# Microcontroller.net
KiCad netlist of a schematic drawn in Altium Designer
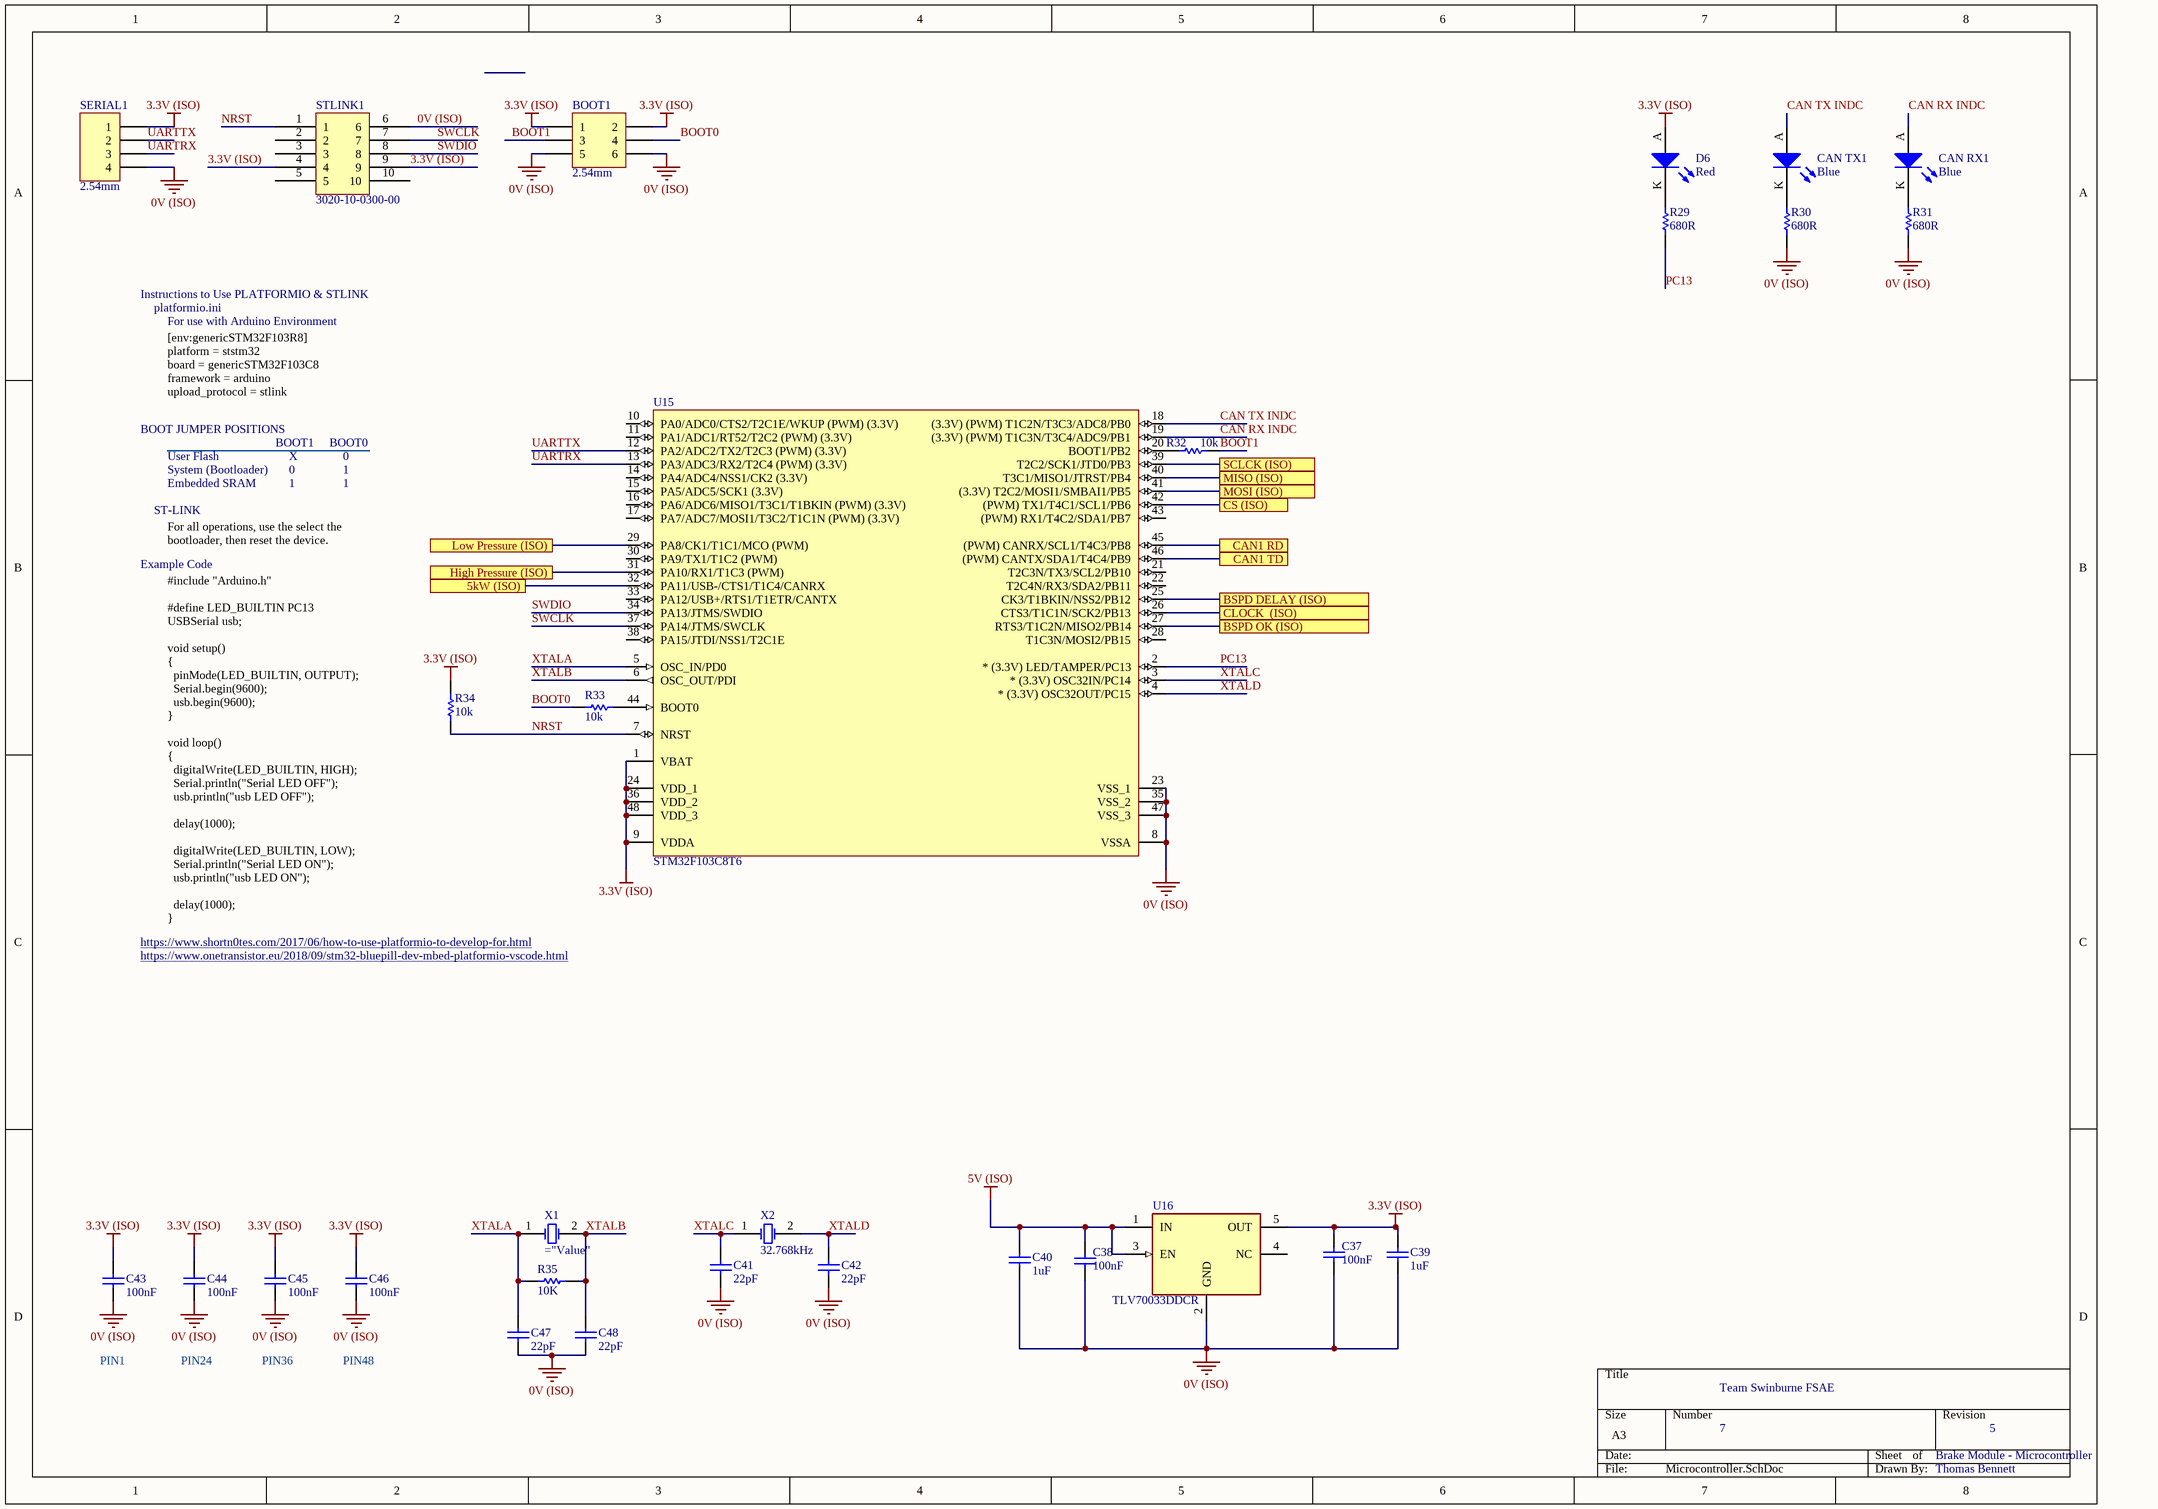
[diagram p0: Microcontroller.SchDoc]

(export (version "E")
  (design (tool "Eeschema 10.0.6"))
  (components
    (comp (ref "BOOT1")
      (value "2.54mm")
      (footprint "TH 2.54mm Header 2x3")
      (fields (field (name "PART NUMBER") "TH 2.54mm Header 2x3") (field (name "CONTACT") "NA"))
      (libsource (lib "ts_20-standard-connectors") (part "Header 2x3"))
    )
    (comp (ref "C37")
      (value "100nF")
      (footprint "C0603")
      (fields (field (name "PART NUMBER") "CC0603ZPY5V9BB104") (field (name "TOLERANCE") "5%"))
      (libsource (lib "AMS_Component_Library") (part "Capacitor"))
    )
    (comp (ref "C38")
      (value "100nF")
      (footprint "C0603")
      (fields (field (name "PART NUMBER") "CC0603ZPY5V9BB104") (field (name "TOLERANCE") "5%"))
      (libsource (lib "AMS_Component_Library") (part "Capacitor"))
    )
    (comp (ref "C39")
      (value "1uF")
      (footprint "0603")
      (fields
        (field (name "PART NUMBER") "GRT188R61H105ME13D")
        (field (name "TOLERANCE") "20%")
        (field (name "MANUFACTURER") "muRata")
      )
      (libsource (lib "ts_20-standard-library") (part "Capacitor"))
    )
    (comp (ref "C40")
      (value "1uF")
      (footprint "0603")
      (fields
        (field (name "PART NUMBER") "GRT188R61H105ME13D")
        (field (name "TOLERANCE") "20%")
        (field (name "MANUFACTURER") "muRata")
      )
      (libsource (lib "ts_20-standard-library") (part "Capacitor"))
    )
    (comp (ref "C41")
      (value "22pF")
      (footprint "C0603")
      (fields (field (name "PART NUMBER") "CC0603JPNPO9BN220") (field (name "TOLERANCE") "5%"))
      (libsource (lib "AMS_Component_Library") (part "Capacitor"))
    )
    (comp (ref "C42")
      (value "22pF")
      (footprint "C0603")
      (fields (field (name "PART NUMBER") "CC0603JPNPO9BN220") (field (name "TOLERANCE") "5%"))
      (libsource (lib "AMS_Component_Library") (part "Capacitor"))
    )
    (comp (ref "C43")
      (value "100nF")
      (footprint "C0603")
      (fields (field (name "PART NUMBER") "CC0603ZPY5V9BB104") (field (name "TOLERANCE") "5%"))
      (libsource (lib "AMS_Component_Library") (part "Capacitor"))
    )
    (comp (ref "C44")
      (value "100nF")
      (footprint "C0603")
      (fields (field (name "PART NUMBER") "CC0603ZPY5V9BB104") (field (name "TOLERANCE") "5%"))
      (libsource (lib "AMS_Component_Library") (part "Capacitor"))
    )
    (comp (ref "C45")
      (value "100nF")
      (footprint "C0603")
      (fields (field (name "PART NUMBER") "CC0603ZPY5V9BB104") (field (name "TOLERANCE") "5%"))
      (libsource (lib "AMS_Component_Library") (part "Capacitor"))
    )
    (comp (ref "C46")
      (value "100nF")
      (footprint "C0603")
      (fields (field (name "PART NUMBER") "CC0603ZPY5V9BB104") (field (name "TOLERANCE") "5%"))
      (libsource (lib "AMS_Component_Library") (part "Capacitor"))
    )
    (comp (ref "C47")
      (value "22pF")
      (footprint "C0603")
      (fields (field (name "PART NUMBER") "CC0603JPNPO9BN220") (field (name "TOLERANCE") "5%"))
      (libsource (lib "AMS_Component_Library") (part "Capacitor"))
    )
    (comp (ref "C48")
      (value "22pF")
      (footprint "C0603")
      (fields (field (name "PART NUMBER") "CC0603JPNPO9BN220") (field (name "TOLERANCE") "5%"))
      (libsource (lib "AMS_Component_Library") (part "Capacitor"))
    )
    (comp (ref "CAN RX1")
      (value "Blue")
      (footprint "0805 LED")
      (description "LED BLUE CLEAR 2012 SMD")
      (fields
        (field (name "PART NUMBER") "SML-MN2BCTT86C")
        (field (name "MANUFACTURER") "ROHM Semiconductor")
      )
      (libsource (lib "ts_20-standard-library") (part "LED"))
    )
    (comp (ref "CAN TX1")
      (value "Blue")
      (footprint "0805 LED")
      (description "LED BLUE CLEAR 2012 SMD")
      (fields
        (field (name "PART NUMBER") "SML-MN2BCTT86C")
        (field (name "MANUFACTURER") "ROHM Semiconductor")
      )
      (libsource (lib "ts_20-standard-library") (part "LED"))
    )
    (comp (ref "D6")
      (value "Red")
      (footprint "0805 LED")
      (description "Red LED Indication - Discrete 1.75V 0805 (2012 Metric)")
      (fields (field (name "PART NUMBER") "SML-210LTT86") (field (name "MANUFACTURER") "ROHM Semiconductor"))
      (libsource (lib "ts_20-standard-library") (part "LED"))
    )
    (comp (ref "R29")
      (value "680R")
      (footprint "R0603")
      (fields (field (name "PART NUMBER") "RCP0603B680RGEA") (field (name "TOLERANCE") "2%"))
      (libsource (lib "AMS_Component_Library") (part "Resistor"))
    )
    (comp (ref "R30")
      (value "680R")
      (footprint "R0603")
      (fields (field (name "PART NUMBER") "RCP0603B680RGEA") (field (name "TOLERANCE") "2%"))
      (libsource (lib "AMS_Component_Library") (part "Resistor"))
    )
    (comp (ref "R31")
      (value "680R")
      (footprint "R0603")
      (fields (field (name "PART NUMBER") "RCP0603B680RGEA") (field (name "TOLERANCE") "2%"))
      (libsource (lib "AMS_Component_Library") (part "Resistor"))
    )
    (comp (ref "R32")
      (value "10k")
      (footprint "0805")
      (fields
        (field (name "PART NUMBER") "RC0805FR0710KL")
        (field (name "MANUFACTURER") "YAGEO")
        (field (name "TOLERANCE") "0.01")
      )
      (libsource (lib "ts_20-standard-library") (part "Resistor"))
    )
    (comp (ref "R33")
      (value "10k")
      (footprint "0805")
      (fields
        (field (name "PART NUMBER") "RC0805FR0710KL")
        (field (name "MANUFACTURER") "YAGEO")
        (field (name "TOLERANCE") "0.01")
      )
      (libsource (lib "ts_20-standard-library") (part "Resistor"))
    )
    (comp (ref "R34")
      (value "10k")
      (footprint "0805")
      (fields
        (field (name "PART NUMBER") "RC0805FR0710KL")
        (field (name "MANUFACTURER") "YAGEO")
        (field (name "TOLERANCE") "0.01")
      )
      (libsource (lib "ts_20-standard-library") (part "Resistor"))
    )
    (comp (ref "R35")
      (value "10K")
      (footprint "R0603")
      (fields (field (name "PART NUMBER") "RA73F1J10KBTD") (field (name "TOLERANCE") "0.1%"))
      (libsource (lib "AMS_Component_Library") (part "Resistor"))
    )
    (comp (ref "SERIAL1")
      (value "2.54mm")
      (footprint "TH 2.54mm Header 1x4")
      (fields (field (name "PART NUMBER") "TH 2.54mm Header 1x4") (field (name "CONTACT") "NA"))
      (libsource (lib "ts_20-standard-connectors") (part "Header 1x4"))
    )
    (comp (ref "STLINK1")
      (value "3020-10-0300-00")
      (footprint "3020-10-0300-00")
      (description "Header SMD 2.54mm 2x05")
      (libsource (lib "AMS_Component_Library") (part "3020-10-0300-00"))
    )
    (comp (ref "U15")
      (value "STM32F103C8T6")
      (footprint "STM 48-LQFP")
      (description "ARM® Cortex®-M3 STM32F1 Microcontroller IC 32-Bit 72MHz 64KB (64K x 8) FLASH")
      (fields
        (field (name "MANUFACTURER") "STMicroelectronics")
        (field (name "DIGIKEY PART NUMBER") "497-6063-ND")
      )
      (libsource (lib "ts_20-standard-library") (part "STM32F103C8T6"))
    )
    (comp (ref "U16")
      (value "TLV70033DDCR")
      (footprint "FP-DDC0005A-IPC_B")
      (description "Fixed Positive LDO Regulator, 3.3V, 0.25V Dropout, PMOS, PDSO5")
      (libsource (lib "Team Swinburne") (part "c6f9311032385d92892323ecfb9e53c"))
    )
    (comp (ref "X1")
      (value "~")
      (footprint "ECS-80-18-30-JGN-TR")
      (description "Crystal 8MHz")
      (fields (field (name "PART NUMBER") "ECS-80-18-30-JGN-TR"))
      (libsource (lib "AMS_Component_Library") (part "Crystal"))
    )
    (comp (ref "X2")
      (value "32.768kHz")
      (footprint "EPSON 2-SMD")
      (fields
        (field (name "PART NUMBER") "FC-135 32.7680KA-A5")
        (field (name "MANUFACTURER") "EPSON")
        (field (name "DIGIKEY PART NUMBER") "SER4103TR-ND")
      )
      (libsource (lib "ts_20-standard-library") (part "Crystal"))
    )
  )
  (nets
    (net (code "1") (name "/5kW (ISO)") (class "Default")
      (node (ref "U15") (pin "32") (pinfunction "PA11/USB-/CTS1/T1C4/CANRX_32") (pintype "bidirectional"))
    )
    (net (code "2") (name "/BOOT0") (class "Default")
      (node (ref "BOOT1") (pin "4") (pinfunction "4_4") (pintype "passive"))
      (node (ref "R33") (pin "1") (pinfunction "1_1") (pintype "passive"))
    )
    (net (code "3") (name "/BOOT1") (class "Default")
      (node (ref "BOOT1") (pin "3") (pinfunction "3_3") (pintype "passive"))
      (node (ref "R32") (pin "2") (pinfunction "2_2") (pintype "passive"))
    )
    (net (code "4") (name "/BSPD DELAY (ISO)") (class "Default")
      (node (ref "U15") (pin "25") (pinfunction "CK3/T1BKIN/NSS2/PB12_25") (pintype "bidirectional"))
    )
    (net (code "5") (name "/BSPD OK (ISO)") (class "Default")
      (node (ref "U15") (pin "27") (pinfunction "RTS3/T1C2N/MISO2/PB14_27") (pintype "bidirectional"))
    )
    (net (code "6") (name "/CAN RX INDC") (class "Default")
      (node (ref "CAN RX1") (pin "A") (pinfunction "A_A") (pintype "passive"))
      (node (ref "U15") (pin "19") (pinfunction "(3.3V)_(PWM)_T1C3N/T3C4/ADC9/PB1_19") (pintype "bidirectional"))
    )
    (net (code "7") (name "/CAN TX INDC") (class "Default")
      (node (ref "CAN TX1") (pin "A") (pinfunction "A_A") (pintype "passive"))
      (node (ref "U15") (pin "18") (pinfunction "(3.3V)_(PWM)_T1C2N/T3C3/ADC8/PB0_18") (pintype "bidirectional"))
    )
    (net (code "8") (name "/CAN1 RD") (class "Default")
      (node (ref "U15") (pin "45") (pinfunction "(PWM)_CANRX/SCL1/T4C3/PB8_45") (pintype "bidirectional"))
    )
    (net (code "9") (name "/CAN1 TD") (class "Default")
      (node (ref "U15") (pin "46") (pinfunction "(PWM)_CANTX/SDA1/T4C4/PB9_46") (pintype "bidirectional"))
    )
    (net (code "10") (name "/CLOCK  (ISO)") (class "Default")
      (node (ref "U15") (pin "26") (pinfunction "CTS3/T1C1N/SCK2/PB13_26") (pintype "bidirectional"))
    )
    (net (code "11") (name "/CS (ISO)") (class "Default")
      (node (ref "U15") (pin "42") (pinfunction "(PWM)_TX1/T4C1/SCL1/PB6_42") (pintype "bidirectional"))
    )
    (net (code "12") (name "/High Pressure (ISO)") (class "Default")
      (node (ref "U15") (pin "31") (pinfunction "PA10/RX1/T1C3_(PWM)_31") (pintype "bidirectional"))
    )
    (net (code "13") (name "/Low Pressure (ISO)") (class "Default")
      (node (ref "U15") (pin "29") (pinfunction "PA8/CK1/T1C1/MCO_(PWM)_29") (pintype "bidirectional"))
    )
    (net (code "14") (name "/MISO (ISO)") (class "Default")
      (node (ref "U15") (pin "40") (pinfunction "T3C1/MISO1/JTRST/PB4_40") (pintype "bidirectional"))
    )
    (net (code "15") (name "/MOSI (ISO)") (class "Default")
      (node (ref "U15") (pin "41") (pinfunction "(3.3V)_T2C2/MOSI1/SMBAI1/PB5_41") (pintype "bidirectional"))
    )
    (net (code "16") (name "/NRST") (class "Default")
      (node (ref "R34") (pin "1") (pinfunction "1_1") (pintype "passive"))
      (node (ref "STLINK1") (pin "1") (pinfunction "1_1") (pintype "passive"))
      (node (ref "U15") (pin "7") (pinfunction "NRST_7") (pintype "bidirectional"))
    )
    (net (code "17") (name "/PC13") (class "Default")
      (node (ref "R29") (pin "2") (pinfunction "2_2") (pintype "passive"))
      (node (ref "U15") (pin "2") (pinfunction "*_(3.3V)_LED/TAMPER/PC13_2") (pintype "bidirectional"))
    )
    (net (code "18") (name "/SCLCK (ISO)") (class "Default")
      (node (ref "U15") (pin "39") (pinfunction "T2C2/SCK1/JTD0/PB3_39") (pintype "bidirectional"))
    )
    (net (code "19") (name "/SWCLK") (class "Default")
      (node (ref "STLINK1") (pin "7") (pinfunction "7_7") (pintype "passive"))
      (node (ref "U15") (pin "37") (pinfunction "PA14/JTMS/SWCLK_37") (pintype "bidirectional"))
    )
    (net (code "20") (name "/SWDIO") (class "Default")
      (node (ref "STLINK1") (pin "8") (pinfunction "8_8") (pintype "passive"))
      (node (ref "U15") (pin "34") (pinfunction "PA13/JTMS/SWDIO_34") (pintype "bidirectional"))
    )
    (net (code "21") (name "/UARTRX") (class "Default")
      (node (ref "SERIAL1") (pin "3") (pinfunction "3_3") (pintype "passive"))
      (node (ref "U15") (pin "13") (pinfunction "PA3/ADC3/RX2/T2C4_(PWM)_(3.3V)_13") (pintype "bidirectional"))
    )
    (net (code "22") (name "/UARTTX") (class "Default")
      (node (ref "SERIAL1") (pin "2") (pinfunction "2_2") (pintype "passive"))
      (node (ref "U15") (pin "12") (pinfunction "PA2/ADC2/TX2/T2C3_(PWM)_(3.3V)_12") (pintype "bidirectional"))
    )
    (net (code "23") (name "/XTALA") (class "Default")
      (node (ref "C47") (pin "2") (pinfunction "2_2") (pintype "passive"))
      (node (ref "R35") (pin "1") (pinfunction "1_1") (pintype "passive"))
      (node (ref "U15") (pin "5") (pinfunction "OSC_IN/PD0_5") (pintype "input"))
      (node (ref "X1") (pin "1") (pinfunction "OSC1_1") (pintype "passive"))
    )
    (net (code "24") (name "/XTALB") (class "Default")
      (node (ref "C48") (pin "2") (pinfunction "2_2") (pintype "passive"))
      (node (ref "R35") (pin "2") (pinfunction "2_2") (pintype "passive"))
      (node (ref "U15") (pin "6") (pinfunction "OSC_OUT/PDI_6") (pintype "output"))
      (node (ref "X1") (pin "2") (pinfunction "OSC2_2") (pintype "passive"))
    )
    (net (code "25") (name "/XTALC") (class "Default")
      (node (ref "C41") (pin "2") (pinfunction "2_2") (pintype "passive"))
      (node (ref "U15") (pin "3") (pinfunction "*_(3.3V)_OSC32IN/PC14_3") (pintype "bidirectional"))
      (node (ref "X2") (pin "1") (pinfunction "OSC1_1") (pintype "passive"))
    )
    (net (code "26") (name "/XTALD") (class "Default")
      (node (ref "C42") (pin "2") (pinfunction "2_2") (pintype "passive"))
      (node (ref "U15") (pin "4") (pinfunction "*_(3.3V)_OSC32OUT/PC15_4") (pintype "bidirectional"))
      (node (ref "X2") (pin "2") (pinfunction "OSC2_2") (pintype "passive"))
    )
    (net (code "27") (name "0V (ISO)") (class "Default")
      (node (ref "BOOT1") (pin "5") (pinfunction "5_5") (pintype "passive"))
      (node (ref "BOOT1") (pin "6") (pinfunction "6_6") (pintype "passive"))
      (node (ref "C37") (pin "1") (pinfunction "1_1") (pintype "passive"))
      (node (ref "C38") (pin "1") (pinfunction "1_1") (pintype "passive"))
      (node (ref "C39") (pin "1") (pinfunction "1_1") (pintype "passive"))
      (node (ref "C40") (pin "1") (pinfunction "1_1") (pintype "passive"))
      (node (ref "C41") (pin "1") (pinfunction "1_1") (pintype "passive"))
      (node (ref "C42") (pin "1") (pinfunction "1_1") (pintype "passive"))
      (node (ref "C43") (pin "1") (pinfunction "1_1") (pintype "passive"))
      (node (ref "C44") (pin "1") (pinfunction "1_1") (pintype "passive"))
      (node (ref "C45") (pin "1") (pinfunction "1_1") (pintype "passive"))
      (node (ref "C46") (pin "1") (pinfunction "1_1") (pintype "passive"))
      (node (ref "C47") (pin "1") (pinfunction "1_1") (pintype "passive"))
      (node (ref "C48") (pin "1") (pinfunction "1_1") (pintype "passive"))
      (node (ref "R30") (pin "2") (pinfunction "2_2") (pintype "passive"))
      (node (ref "R31") (pin "2") (pinfunction "2_2") (pintype "passive"))
      (node (ref "SERIAL1") (pin "4") (pinfunction "4_4") (pintype "passive"))
      (node (ref "STLINK1") (pin "6") (pinfunction "6_6") (pintype "passive"))
      (node (ref "U15") (pin "23") (pinfunction "VSS_1_23") (pintype "power_in"))
      (node (ref "U15") (pin "35") (pinfunction "VSS_2_35") (pintype "power_in"))
      (node (ref "U15") (pin "47") (pinfunction "VSS_3_47") (pintype "power_in"))
      (node (ref "U15") (pin "8") (pinfunction "VSSA_8") (pintype "power_in"))
      (node (ref "U16") (pin "2") (pinfunction "GND_2") (pintype "power_in"))
    )
    (net (code "28") (name "3.3V (ISO)") (class "Default")
      (node (ref "BOOT1") (pin "1") (pinfunction "1_1") (pintype "passive"))
      (node (ref "BOOT1") (pin "2") (pinfunction "2_2") (pintype "passive"))
      (node (ref "C37") (pin "2") (pinfunction "2_2") (pintype "passive"))
      (node (ref "C39") (pin "2") (pinfunction "2_2") (pintype "passive"))
      (node (ref "C43") (pin "2") (pinfunction "2_2") (pintype "passive"))
      (node (ref "C44") (pin "2") (pinfunction "2_2") (pintype "passive"))
      (node (ref "C45") (pin "2") (pinfunction "2_2") (pintype "passive"))
      (node (ref "C46") (pin "2") (pinfunction "2_2") (pintype "passive"))
      (node (ref "D6") (pin "A") (pinfunction "A_A") (pintype "passive"))
      (node (ref "R34") (pin "2") (pinfunction "2_2") (pintype "passive"))
      (node (ref "SERIAL1") (pin "1") (pinfunction "1_1") (pintype "passive"))
      (node (ref "STLINK1") (pin "4") (pinfunction "4_4") (pintype "passive"))
      (node (ref "STLINK1") (pin "9") (pinfunction "9_9") (pintype "passive"))
      (node (ref "U15") (pin "1") (pinfunction "VBAT_1") (pintype "power_in"))
      (node (ref "U15") (pin "24") (pinfunction "VDD_1_24") (pintype "power_in"))
      (node (ref "U15") (pin "36") (pinfunction "VDD_2_36") (pintype "power_in"))
      (node (ref "U15") (pin "48") (pinfunction "VDD_3_48") (pintype "power_in"))
      (node (ref "U15") (pin "9") (pinfunction "VDDA_9") (pintype "power_in"))
      (node (ref "U16") (pin "5") (pinfunction "OUT_5") (pintype "power_in"))
    )
    (net (code "29") (name "5V (ISO)") (class "Default")
      (node (ref "C38") (pin "2") (pinfunction "2_2") (pintype "passive"))
      (node (ref "C40") (pin "2") (pinfunction "2_2") (pintype "passive"))
      (node (ref "U16") (pin "1") (pinfunction "IN_1") (pintype "power_in"))
      (node (ref "U16") (pin "3") (pinfunction "EN_3") (pintype "input"))
    )
    (net (code "30") (name "Net-(CAN RX1-PadK)") (class "Default")
      (node (ref "CAN RX1") (pin "K") (pinfunction "K_K") (pintype "passive"))
      (node (ref "R31") (pin "1") (pinfunction "1_1") (pintype "passive"))
    )
    (net (code "31") (name "Net-(CAN TX1-PadK)") (class "Default")
      (node (ref "CAN TX1") (pin "K") (pinfunction "K_K") (pintype "passive"))
      (node (ref "R30") (pin "1") (pinfunction "1_1") (pintype "passive"))
    )
    (net (code "32") (name "Net-(D6-PadK)") (class "Default")
      (node (ref "D6") (pin "K") (pinfunction "K_K") (pintype "passive"))
      (node (ref "R29") (pin "1") (pinfunction "1_1") (pintype "passive"))
    )
    (net (code "33") (name "Net-(U15-BOOT0)") (class "Default")
      (node (ref "R33") (pin "2") (pinfunction "2_2") (pintype "passive"))
      (node (ref "U15") (pin "44") (pinfunction "BOOT0_44") (pintype "input"))
    )
    (net (code "34") (name "Net-(U15-BOOT1{slash}PB2)") (class "Default")
      (node (ref "R32") (pin "1") (pinfunction "1_1") (pintype "passive"))
      (node (ref "U15") (pin "20") (pinfunction "BOOT1/PB2_20") (pintype "bidirectional"))
    )
    (net (code "35") (name "unconnected-(STLINK1-Pad2)") (class "Default")
      (node (ref "STLINK1") (pin "2") (pinfunction "2_2") (pintype "passive"))
    )
    (net (code "36") (name "unconnected-(STLINK1-Pad3)") (class "Default")
      (node (ref "STLINK1") (pin "3") (pinfunction "3_3") (pintype "passive"))
    )
    (net (code "37") (name "unconnected-(STLINK1-Pad5)") (class "Default")
      (node (ref "STLINK1") (pin "5") (pinfunction "5_5") (pintype "passive"))
    )
    (net (code "38") (name "unconnected-(STLINK1-Pad10)") (class "Default")
      (node (ref "STLINK1") (pin "10") (pinfunction "10_10") (pintype "passive"))
    )
    (net (code "39") (name "unconnected-(U15-(PWM)_RX1{slash}T4C2{slash}SDA1{slash}PB7-Pad43)") (class "Default")
      (node (ref "U15") (pin "43") (pinfunction "(PWM)_RX1/T4C2/SDA1/PB7_43") (pintype "bidirectional"))
    )
    (net (code "40") (name "unconnected-(U15-PA0{slash}ADC0{slash}CTS2{slash}T2C1E{slash}WKUP_(PWM)_(3.3V)-Pad10)") (class "Default")
      (node (ref "U15") (pin "10") (pinfunction "PA0/ADC0/CTS2/T2C1E/WKUP_(PWM)_(3.3V)_10") (pintype "bidirectional"))
    )
    (net (code "41") (name "unconnected-(U15-PA1{slash}ADC1{slash}RT52{slash}T2C2_(PWM)_(3.3V)-Pad11)") (class "Default")
      (node (ref "U15") (pin "11") (pinfunction "PA1/ADC1/RT52/T2C2_(PWM)_(3.3V)_11") (pintype "bidirectional"))
    )
    (net (code "42") (name "unconnected-(U15-PA4{slash}ADC4{slash}NSS1{slash}CK2_(3.3V)-Pad14)") (class "Default")
      (node (ref "U15") (pin "14") (pinfunction "PA4/ADC4/NSS1/CK2_(3.3V)_14") (pintype "bidirectional"))
    )
    (net (code "43") (name "unconnected-(U15-PA5{slash}ADC5{slash}SCK1_(3.3V)-Pad15)") (class "Default")
      (node (ref "U15") (pin "15") (pinfunction "PA5/ADC5/SCK1_(3.3V)_15") (pintype "bidirectional"))
    )
    (net (code "44") (name "unconnected-(U15-PA6{slash}ADC6{slash}MISO1{slash}T3C1{slash}T1BKIN_(PWM)_(3.3V)-Pad16)") (class "Default")
      (node (ref "U15") (pin "16") (pinfunction "PA6/ADC6/MISO1/T3C1/T1BKIN_(PWM)_(3.3V)_16") (pintype "bidirectional"))
    )
    (net (code "45") (name "unconnected-(U15-PA7{slash}ADC7{slash}MOSI1{slash}T3C2{slash}T1C1N_(PWM)_(3.3V)-Pad17)") (class "Default")
      (node (ref "U15") (pin "17") (pinfunction "PA7/ADC7/MOSI1/T3C2/T1C1N_(PWM)_(3.3V)_17") (pintype "bidirectional"))
    )
    (net (code "46") (name "unconnected-(U15-PA9{slash}TX1{slash}T1C2_(PWM)-Pad30)") (class "Default")
      (node (ref "U15") (pin "30") (pinfunction "PA9/TX1/T1C2_(PWM)_30") (pintype "bidirectional"))
    )
    (net (code "47") (name "unconnected-(U15-PA12{slash}USB+{slash}RTS1{slash}T1ETR{slash}CANTX-Pad33)") (class "Default")
      (node (ref "U15") (pin "33") (pinfunction "PA12/USB+/RTS1/T1ETR/CANTX_33") (pintype "bidirectional"))
    )
    (net (code "48") (name "unconnected-(U15-PA15{slash}JTDI{slash}NSS1{slash}T2C1E-Pad38)") (class "Default")
      (node (ref "U15") (pin "38") (pinfunction "PA15/JTDI/NSS1/T2C1E_38") (pintype "bidirectional"))
    )
    (net (code "49") (name "unconnected-(U15-T1C3N{slash}MOSI2{slash}PB15-Pad28)") (class "Default")
      (node (ref "U15") (pin "28") (pinfunction "T1C3N/MOSI2/PB15_28") (pintype "bidirectional"))
    )
    (net (code "50") (name "unconnected-(U15-T2C3N{slash}TX3{slash}SCL2{slash}PB10-Pad21)") (class "Default")
      (node (ref "U15") (pin "21") (pinfunction "T2C3N/TX3/SCL2/PB10_21") (pintype "bidirectional"))
    )
    (net (code "51") (name "unconnected-(U15-T2C4N{slash}RX3{slash}SDA2{slash}PB11-Pad22)") (class "Default")
      (node (ref "U15") (pin "22") (pinfunction "T2C4N/RX3/SDA2/PB11_22") (pintype "bidirectional"))
    )
    (net (code "52") (name "unconnected-(U16-NC-Pad4)") (class "Default")
      (node (ref "U16") (pin "4") (pinfunction "NC_4") (pintype "passive"))
    )
  )
)
